# ProPrj___2024-10-24-09-19-47.net
KiCad netlist of a schematic drawn in EasyEDA Pro
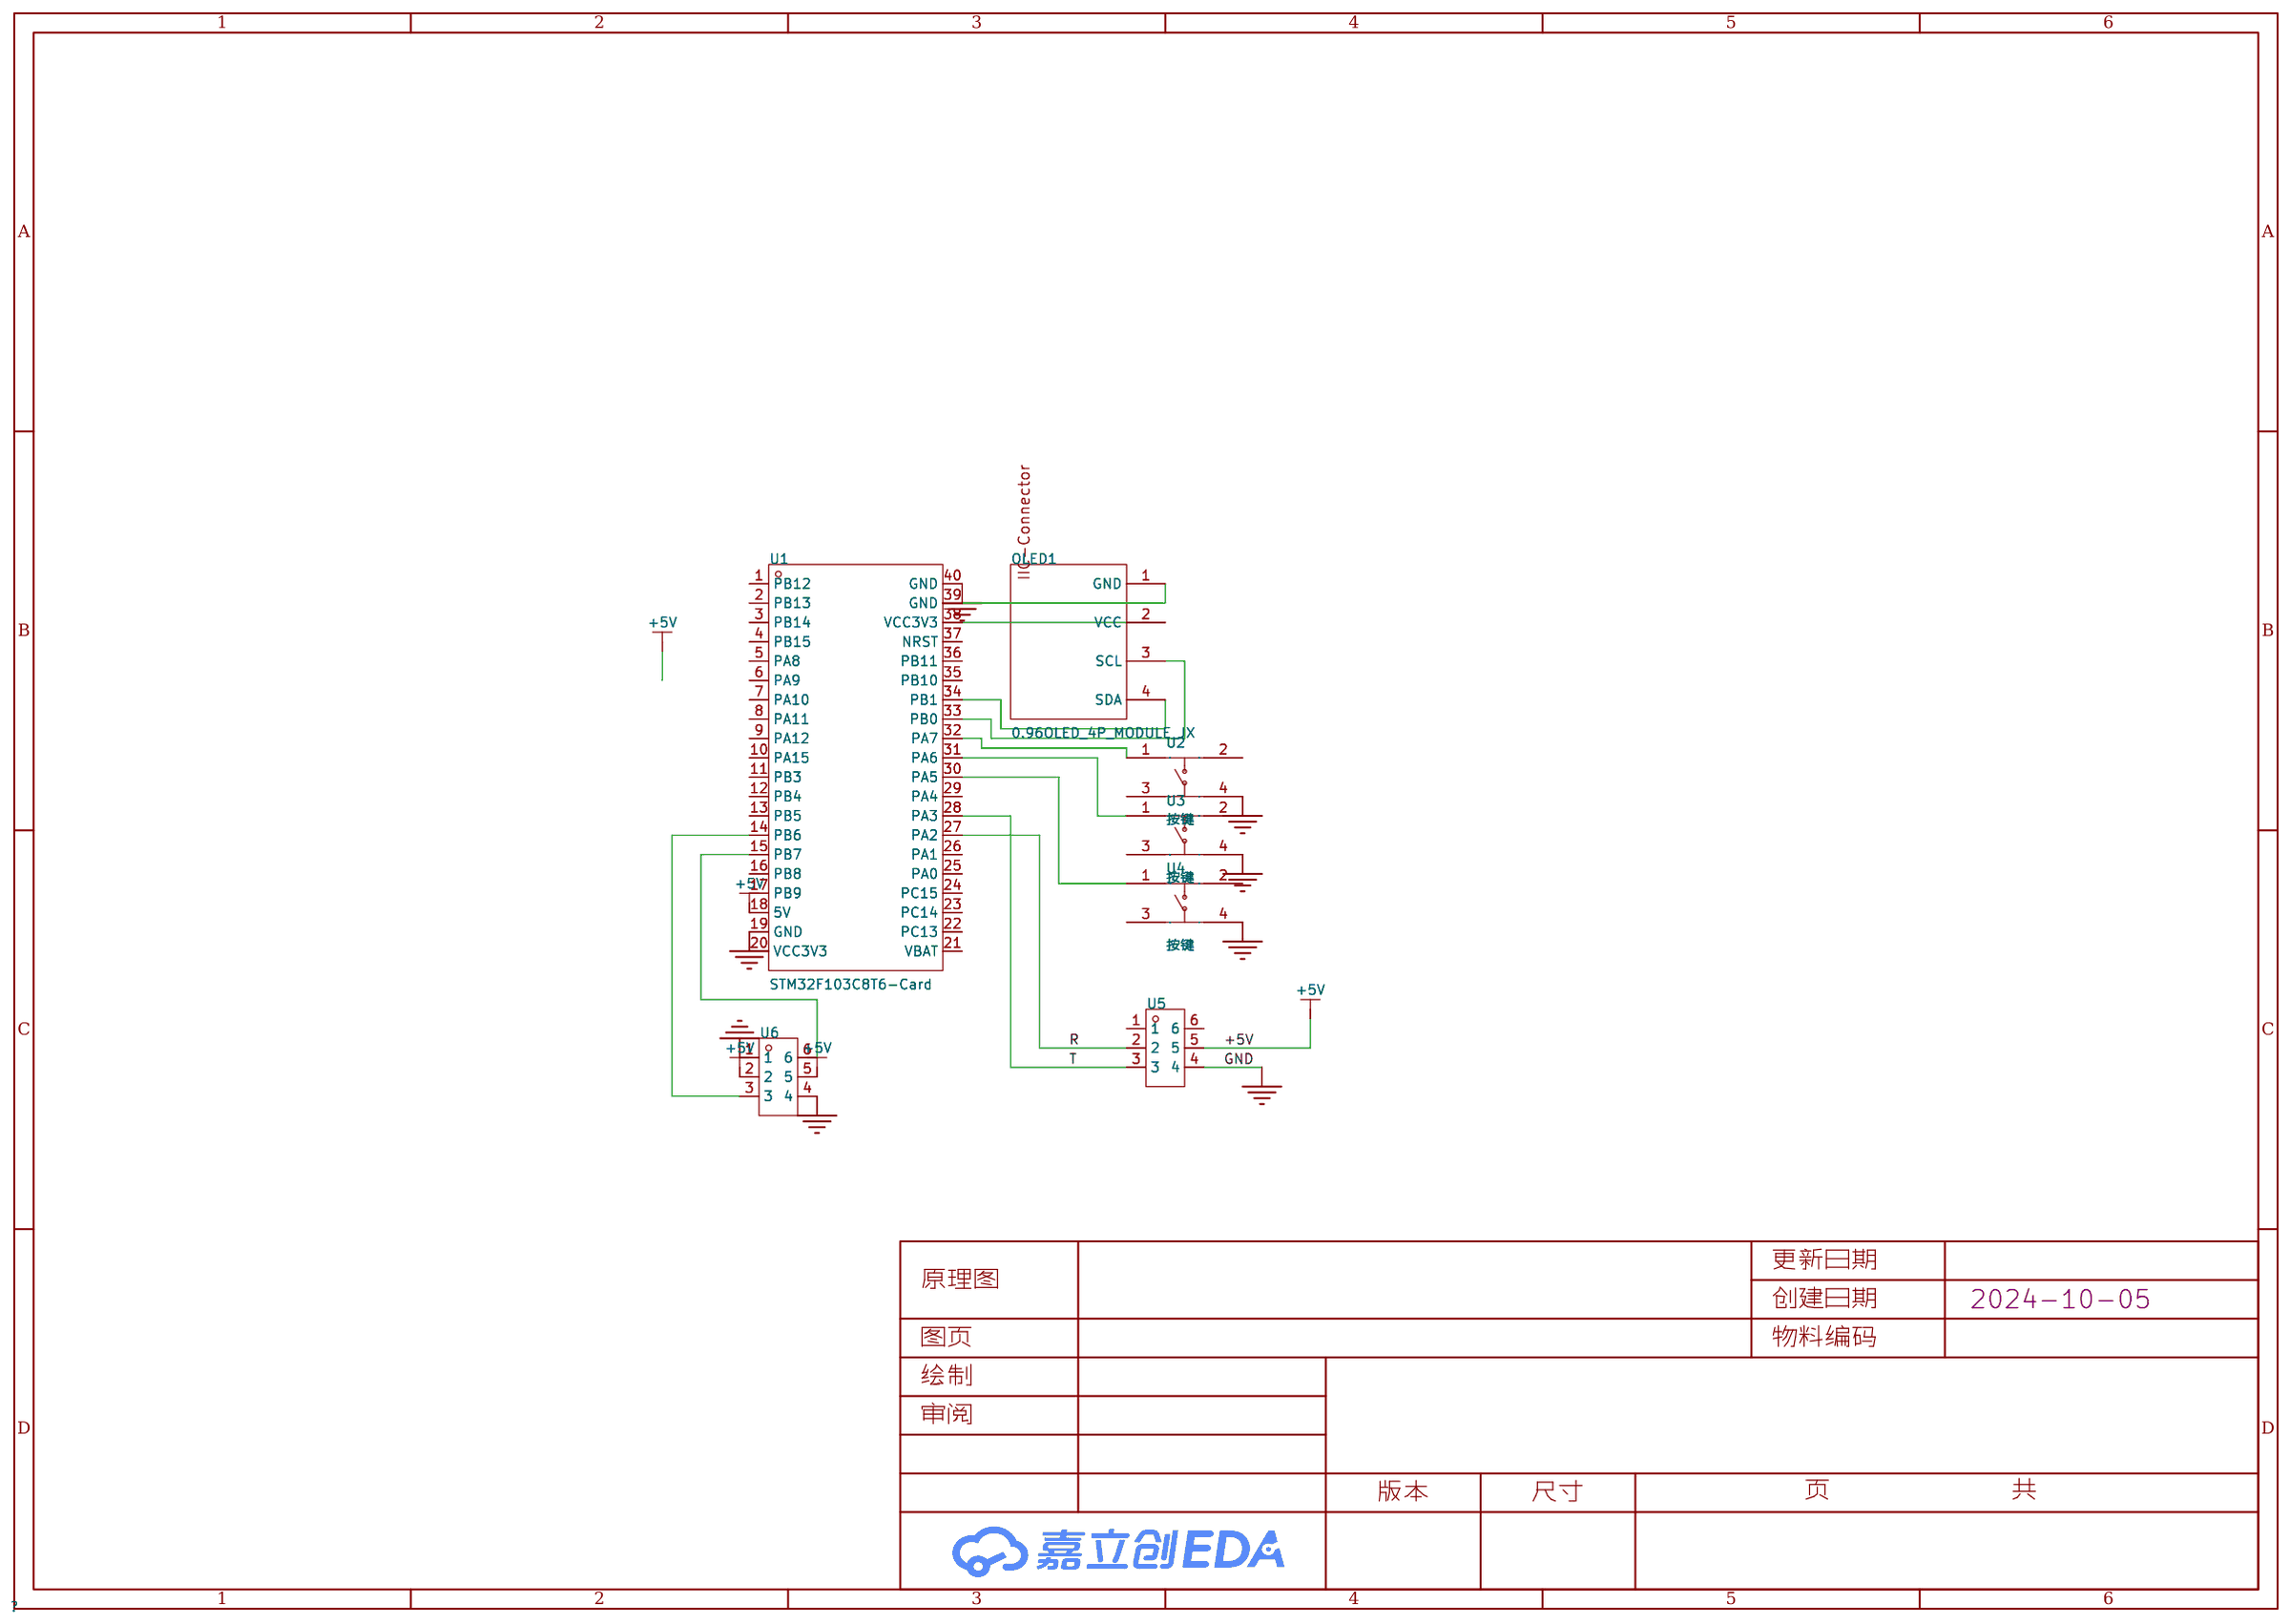
[diagram p0: schematic sheet]

(export (version "E")
  (design (tool "Eeschema 10.0.6"))
  (components
    (comp (ref "OLED1")
      (value "0.96OLED_4P_MODULE_JX")
      (footprint "easyedapro:0.96OLED_4P")
      (libsource (lib "easyedapro") (part "0.96oled_4p_module_jx"))
    )
    (comp (ref "U1")
      (value "STM32F103C8T6-Card")
      (footprint "easyedapro:CONN-TH_L53.3-W22.9_STM32F103C8T6-CARD")
      (libsource (lib "easyedapro") (part "STM32F103C8T6-CARD"))
    )
    (comp (ref "U2")
      (value "按键")
      (footprint "easyedapro:SW-SMD_4P-L6.0-W6.0-P4.50-LS9.0-2")
      (libsource (lib "easyedapro") (part "SW"))
    )
    (comp (ref "U3")
      (value "按键")
      (footprint "easyedapro:SW-SMD_4P-L6.0-W6.0-P4.50-LS9.0-2")
      (libsource (lib "easyedapro") (part "SW"))
    )
    (comp (ref "U4")
      (value "按键")
      (footprint "easyedapro:SW-SMD_4P-L6.0-W6.0-P4.50-LS9.0-2")
      (libsource (lib "easyedapro") (part "SW"))
    )
    (comp (ref "U5")
      (value "BL")
      (footprint "easyedapro:HDR-TH_6P-P2.54-V-F-2")
      (fields (field (name "Manufacturer Part") "OLED-6PIN"))
      (libsource (lib "easyedapro") (part "OLED-6PIN"))
    )
    (comp (ref "U6")
      (value "BL")
      (footprint "easyedapro:HDR-TH_6P-P2.54-V-F-2")
      (fields (field (name "Manufacturer Part") "OLED-6PIN"))
      (libsource (lib "easyedapro") (part "OLED-6PIN"))
    )
  )
  (nets
    (net (code "1") (name "+5V") (class "Default")
      (node (ref "U1") (pin "18") (pinfunction "5V_18") (pintype "unspecified"))
      (node (ref "U5") (pin "5") (pinfunction "5_5") (pintype "unspecified"))
      (node (ref "U6") (pin "2") (pinfunction "2_2") (pintype "unspecified"))
      (node (ref "U6") (pin "5") (pinfunction "5_5") (pintype "unspecified"))
    )
    (net (code "2") (name "/R") (class "Default")
      (node (ref "U1") (pin "27") (pinfunction "PA2_27") (pintype "unspecified"))
      (node (ref "U5") (pin "2") (pinfunction "2_2") (pintype "unspecified"))
    )
    (net (code "3") (name "/T") (class "Default")
      (node (ref "U1") (pin "28") (pinfunction "PA3_28") (pintype "unspecified"))
      (node (ref "U5") (pin "3") (pinfunction "3_3") (pintype "unspecified"))
    )
    (net (code "4") (name "GND") (class "Default")
      (node (ref "U1") (pin "19") (pinfunction "GND_19") (pintype "unspecified"))
      (node (ref "U1") (pin "40") (pinfunction "GND_40") (pintype "unspecified"))
      (node (ref "U2") (pin "4") (pinfunction "4_4") (pintype "input"))
      (node (ref "U3") (pin "4") (pinfunction "4_4") (pintype "input"))
      (node (ref "U4") (pin "4") (pinfunction "4_4") (pintype "input"))
      (node (ref "U5") (pin "4") (pinfunction "4_4") (pintype "unspecified"))
      (node (ref "U6") (pin "1") (pinfunction "1_1") (pintype "unspecified"))
      (node (ref "U6") (pin "4") (pinfunction "4_4") (pintype "unspecified"))
    )
    (net (code "5") (name "Net-(OLED1-GND)") (class "Default")
      (node (ref "OLED1") (pin "1") (pinfunction "GND_1") (pintype "unspecified"))
      (node (ref "U1") (pin "39") (pinfunction "GND_39") (pintype "unspecified"))
    )
    (net (code "6") (name "Net-(OLED1-SCL)") (class "Default")
      (node (ref "OLED1") (pin "3") (pinfunction "SCL_3") (pintype "unspecified"))
      (node (ref "U1") (pin "33") (pinfunction "PB0_33") (pintype "unspecified"))
    )
    (net (code "7") (name "Net-(OLED1-SDA)") (class "Default")
      (node (ref "OLED1") (pin "4") (pinfunction "SDA_4") (pintype "unspecified"))
      (node (ref "U1") (pin "34") (pinfunction "PB1_34") (pintype "unspecified"))
    )
    (net (code "8") (name "Net-(OLED1-VCC)") (class "Default")
      (node (ref "OLED1") (pin "2") (pinfunction "VCC_2") (pintype "unspecified"))
      (node (ref "U1") (pin "38") (pinfunction "VCC3V3_38") (pintype "unspecified"))
    )
    (net (code "9") (name "Net-(U1-PA5)") (class "Default")
      (node (ref "U1") (pin "30") (pinfunction "PA5_30") (pintype "unspecified"))
      (node (ref "U4") (pin "1") (pinfunction "1_1") (pintype "input"))
    )
    (net (code "10") (name "Net-(U1-PA6)") (class "Default")
      (node (ref "U1") (pin "31") (pinfunction "PA6_31") (pintype "unspecified"))
      (node (ref "U3") (pin "1") (pinfunction "1_1") (pintype "input"))
    )
    (net (code "11") (name "Net-(U1-PA7)") (class "Default")
      (node (ref "U1") (pin "32") (pinfunction "PA7_32") (pintype "unspecified"))
      (node (ref "U2") (pin "1") (pinfunction "1_1") (pintype "input"))
    )
    (net (code "12") (name "Net-(U1-PB6)") (class "Default")
      (node (ref "U1") (pin "14") (pinfunction "PB6_14") (pintype "unspecified"))
      (node (ref "U6") (pin "3") (pinfunction "3_3") (pintype "unspecified"))
    )
    (net (code "13") (name "Net-(U1-PB7)") (class "Default")
      (node (ref "U1") (pin "15") (pinfunction "PB7_15") (pintype "unspecified"))
      (node (ref "U6") (pin "6") (pinfunction "6_6") (pintype "unspecified"))
    )
    (net (code "14") (name "unconnected-(U1-NRST-Pad37)") (class "Default")
      (node (ref "U1") (pin "37") (pinfunction "NRST_37") (pintype "unspecified"))
    )
    (net (code "15") (name "unconnected-(U1-PA0-Pad25)") (class "Default")
      (node (ref "U1") (pin "25") (pinfunction "PA0_25") (pintype "unspecified"))
    )
    (net (code "16") (name "unconnected-(U1-PA1-Pad26)") (class "Default")
      (node (ref "U1") (pin "26") (pinfunction "PA1_26") (pintype "unspecified"))
    )
    (net (code "17") (name "unconnected-(U1-PA4-Pad29)") (class "Default")
      (node (ref "U1") (pin "29") (pinfunction "PA4_29") (pintype "unspecified"))
    )
    (net (code "18") (name "unconnected-(U1-PA8-Pad5)") (class "Default")
      (node (ref "U1") (pin "5") (pinfunction "PA8_5") (pintype "unspecified"))
    )
    (net (code "19") (name "unconnected-(U1-PA9-Pad6)") (class "Default")
      (node (ref "U1") (pin "6") (pinfunction "PA9_6") (pintype "unspecified"))
    )
    (net (code "20") (name "unconnected-(U1-PA10-Pad7)") (class "Default")
      (node (ref "U1") (pin "7") (pinfunction "PA10_7") (pintype "unspecified"))
    )
    (net (code "21") (name "unconnected-(U1-PA11-Pad8)") (class "Default")
      (node (ref "U1") (pin "8") (pinfunction "PA11_8") (pintype "unspecified"))
    )
    (net (code "22") (name "unconnected-(U1-PA12-Pad9)") (class "Default")
      (node (ref "U1") (pin "9") (pinfunction "PA12_9") (pintype "unspecified"))
    )
    (net (code "23") (name "unconnected-(U1-PA15-Pad10)") (class "Default")
      (node (ref "U1") (pin "10") (pinfunction "PA15_10") (pintype "unspecified"))
    )
    (net (code "24") (name "unconnected-(U1-PB3-Pad11)") (class "Default")
      (node (ref "U1") (pin "11") (pinfunction "PB3_11") (pintype "unspecified"))
    )
    (net (code "25") (name "unconnected-(U1-PB4-Pad12)") (class "Default")
      (node (ref "U1") (pin "12") (pinfunction "PB4_12") (pintype "unspecified"))
    )
    (net (code "26") (name "unconnected-(U1-PB5-Pad13)") (class "Default")
      (node (ref "U1") (pin "13") (pinfunction "PB5_13") (pintype "unspecified"))
    )
    (net (code "27") (name "unconnected-(U1-PB8-Pad16)") (class "Default")
      (node (ref "U1") (pin "16") (pinfunction "PB8_16") (pintype "unspecified"))
    )
    (net (code "28") (name "unconnected-(U1-PB9-Pad17)") (class "Default")
      (node (ref "U1") (pin "17") (pinfunction "PB9_17") (pintype "unspecified"))
    )
    (net (code "29") (name "unconnected-(U1-PB10-Pad35)") (class "Default")
      (node (ref "U1") (pin "35") (pinfunction "PB10_35") (pintype "unspecified"))
    )
    (net (code "30") (name "unconnected-(U1-PB11-Pad36)") (class "Default")
      (node (ref "U1") (pin "36") (pinfunction "PB11_36") (pintype "unspecified"))
    )
    (net (code "31") (name "unconnected-(U1-PB12-Pad1)") (class "Default")
      (node (ref "U1") (pin "1") (pinfunction "PB12_1") (pintype "unspecified"))
    )
    (net (code "32") (name "unconnected-(U1-PB13-Pad2)") (class "Default")
      (node (ref "U1") (pin "2") (pinfunction "PB13_2") (pintype "unspecified"))
    )
    (net (code "33") (name "unconnected-(U1-PB14-Pad3)") (class "Default")
      (node (ref "U1") (pin "3") (pinfunction "PB14_3") (pintype "unspecified"))
    )
    (net (code "34") (name "unconnected-(U1-PB15-Pad4)") (class "Default")
      (node (ref "U1") (pin "4") (pinfunction "PB15_4") (pintype "unspecified"))
    )
    (net (code "35") (name "unconnected-(U1-PC13-Pad22)") (class "Default")
      (node (ref "U1") (pin "22") (pinfunction "PC13_22") (pintype "unspecified"))
    )
    (net (code "36") (name "unconnected-(U1-PC14-Pad23)") (class "Default")
      (node (ref "U1") (pin "23") (pinfunction "PC14_23") (pintype "unspecified"))
    )
    (net (code "37") (name "unconnected-(U1-PC15-Pad24)") (class "Default")
      (node (ref "U1") (pin "24") (pinfunction "PC15_24") (pintype "unspecified"))
    )
    (net (code "38") (name "unconnected-(U1-VBAT-Pad21)") (class "Default")
      (node (ref "U1") (pin "21") (pinfunction "VBAT_21") (pintype "unspecified"))
    )
    (net (code "39") (name "unconnected-(U1-VCC3V3-Pad20)") (class "Default")
      (node (ref "U1") (pin "20") (pinfunction "VCC3V3_20") (pintype "unspecified"))
    )
    (net (code "40") (name "unconnected-(U2-Pad2)") (class "Default")
      (node (ref "U2") (pin "2") (pinfunction "2_2") (pintype "input"))
    )
    (net (code "41") (name "unconnected-(U2-Pad3)") (class "Default")
      (node (ref "U2") (pin "3") (pinfunction "3_3") (pintype "input"))
    )
    (net (code "42") (name "unconnected-(U3-Pad2)") (class "Default")
      (node (ref "U3") (pin "2") (pinfunction "2_2") (pintype "input"))
    )
    (net (code "43") (name "unconnected-(U3-Pad3)") (class "Default")
      (node (ref "U3") (pin "3") (pinfunction "3_3") (pintype "input"))
    )
    (net (code "44") (name "unconnected-(U4-Pad2)") (class "Default")
      (node (ref "U4") (pin "2") (pinfunction "2_2") (pintype "input"))
    )
    (net (code "45") (name "unconnected-(U4-Pad3)") (class "Default")
      (node (ref "U4") (pin "3") (pinfunction "3_3") (pintype "input"))
    )
    (net (code "46") (name "unconnected-(U5-Pad1)") (class "Default")
      (node (ref "U5") (pin "1") (pinfunction "1_1") (pintype "unspecified"))
    )
    (net (code "47") (name "unconnected-(U5-Pad6)") (class "Default")
      (node (ref "U5") (pin "6") (pinfunction "6_6") (pintype "unspecified"))
    )
  )
)
